# 05.net
KiCad netlist of a schematic drawn in Altium Designer
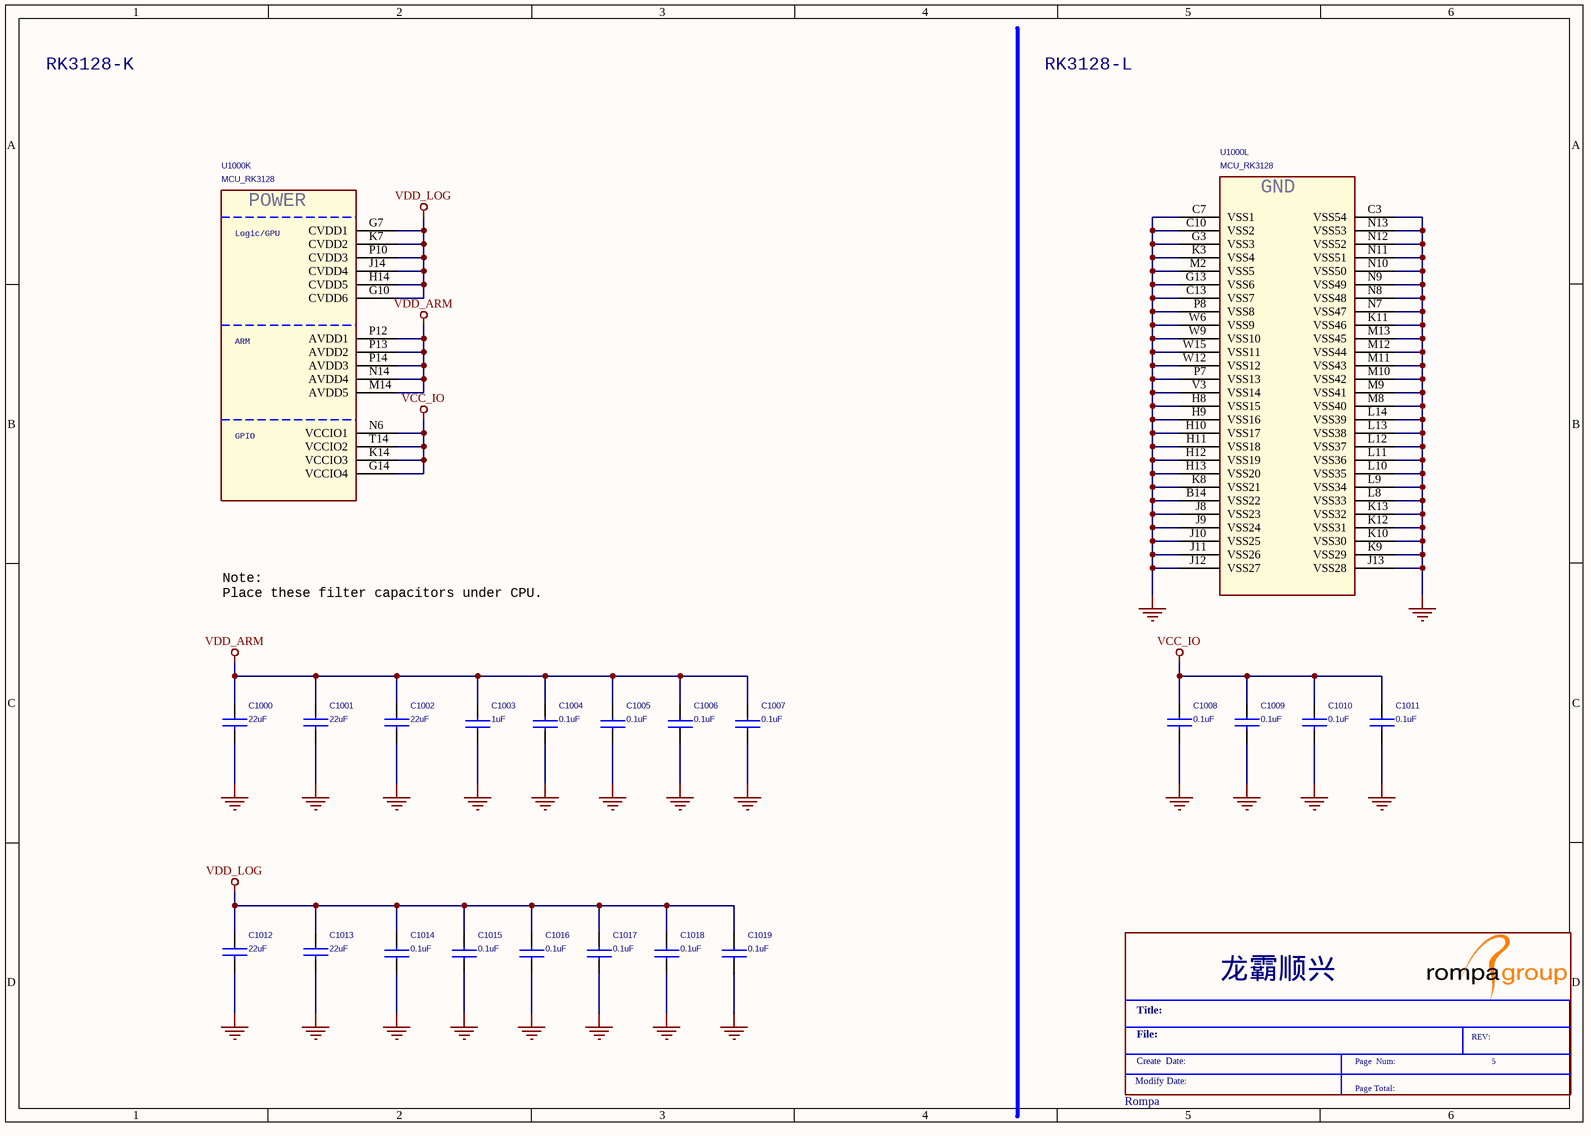
[diagram p0: 05.SchDoc]

(export (version "E")
  (design (tool "Eeschema 10.0.6"))
  (components
    (comp (ref "*")
      (value "Rompa")
      (fields (field (name "SCHEMATIC PAGE NUMBER") "5"))
      (libsource (lib "RK3128_BETA_V03_20151231_Library") (part "Rompa"))
    )
    (comp (ref "C1000")
      (value "22uF")
      (footprint "C0402")
      (description "RoHS CHIP CAP 22uF +10/-10% X5R")
      (libsource (lib "*") (part "CAP NP"))
    )
    (comp (ref "C1001")
      (value "22uF")
      (footprint "C0402")
      (description "RoHS CHIP CAP 22uF +10/-10% X5R")
      (libsource (lib "*") (part "CAP NP"))
    )
    (comp (ref "C1002")
      (value "22uF")
      (footprint "C0402")
      (description "RoHS CHIP CAP 22uF +10/-10% X5R")
      (libsource (lib "*") (part "CAP NP"))
    )
    (comp (ref "C1003")
      (value "1uF")
      (footprint "C0402")
      (description "RoHS CHIP CAP 1uF +10/-10% X5R")
      (libsource (lib "*") (part "CAP NP"))
    )
    (comp (ref "C1004")
      (value "0.1uF")
      (footprint "C0402")
      (description "RoHS CHIP CAP 0.1uF +10/-10% X7R")
      (libsource (lib "*") (part "CAP NP"))
    )
    (comp (ref "C1005")
      (value "0.1uF")
      (footprint "C0402")
      (description "RoHS CHIP CAP 0.1uF +10/-10% X7R")
      (libsource (lib "*") (part "CAP NP"))
    )
    (comp (ref "C1006")
      (value "0.1uF")
      (footprint "C0402")
      (description "RoHS CHIP CAP 0.1uF +10/-10% X7R")
      (libsource (lib "*") (part "CAP NP"))
    )
    (comp (ref "C1007")
      (value "0.1uF")
      (footprint "C0402")
      (description "RoHS CHIP CAP 0.1uF +10/-10% X7R")
      (libsource (lib "*") (part "CAP NP"))
    )
    (comp (ref "C1008")
      (value "0.1uF")
      (footprint "C0402")
      (description "RoHS CHIP CAP 0.1uF +10/-10% X7R")
      (libsource (lib "*") (part "CAP NP"))
    )
    (comp (ref "C1009")
      (value "0.1uF")
      (footprint "C0402")
      (description "RoHS CHIP CAP 0.1uF +10/-10% X7R")
      (libsource (lib "*") (part "CAP NP"))
    )
    (comp (ref "C1010")
      (value "0.1uF")
      (footprint "C0402")
      (description "RoHS CHIP CAP 0.1uF +10/-10% X7R")
      (libsource (lib "*") (part "CAP NP"))
    )
    (comp (ref "C1011")
      (value "0.1uF")
      (footprint "C0402")
      (description "RoHS CHIP CAP 0.1uF +10/-10% X7R")
      (libsource (lib "*") (part "CAP NP"))
    )
    (comp (ref "C1012")
      (value "22uF")
      (footprint "C0402")
      (description "RoHS CHIP CAP 22uF +10/-10% X5R")
      (libsource (lib "*") (part "CAP NP"))
    )
    (comp (ref "C1013")
      (value "22uF")
      (footprint "C0402")
      (description "RoHS CHIP CAP 22uF +10/-10% X5R")
      (libsource (lib "*") (part "CAP NP"))
    )
    (comp (ref "C1014")
      (value "0.1uF")
      (footprint "C0402")
      (description "RoHS CHIP CAP 0.1uF +10/-10% X7R")
      (libsource (lib "*") (part "CAP NP"))
    )
    (comp (ref "C1015")
      (value "0.1uF")
      (footprint "C0402")
      (description "RoHS CHIP CAP 0.1uF +10/-10% X7R")
      (libsource (lib "*") (part "CAP NP"))
    )
    (comp (ref "C1016")
      (value "0.1uF")
      (footprint "C0402")
      (description "RoHS CHIP CAP 0.1uF +10/-10% X7R")
      (libsource (lib "*") (part "CAP NP"))
    )
    (comp (ref "C1017")
      (value "0.1uF")
      (footprint "C0402")
      (description "RoHS CHIP CAP 0.1uF +10/-10% X7R")
      (libsource (lib "*") (part "CAP NP"))
    )
    (comp (ref "C1018")
      (value "0.1uF")
      (footprint "C0402")
      (description "RoHS CHIP CAP 0.1uF +10/-10% X7R")
      (libsource (lib "*") (part "CAP NP"))
    )
    (comp (ref "C1019")
      (value "0.1uF")
      (footprint "C0402")
      (description "RoHS CHIP CAP 0.1uF +10/-10% X7R")
      (libsource (lib "*") (part "CAP NP"))
    )
    (comp (ref "U1000")
      (value "MCU_RK3128")
      (footprint "BGA316-14X14-0.65")
      (libsource (lib "*") (part "MCU_RK3128"))
    )
  )
  (nets
    (net (code "1") (name "GND") (class "Default")
      (node (ref "C1000") (pin "2") (pinfunction "2_2") (pintype "passive"))
      (node (ref "C1001") (pin "2") (pinfunction "2_2") (pintype "passive"))
      (node (ref "C1002") (pin "2") (pinfunction "2_2") (pintype "passive"))
      (node (ref "C1003") (pin "1") (pinfunction "1_1") (pintype "passive"))
      (node (ref "C1004") (pin "1") (pinfunction "1_1") (pintype "passive"))
      (node (ref "C1005") (pin "1") (pinfunction "1_1") (pintype "passive"))
      (node (ref "C1006") (pin "1") (pinfunction "1_1") (pintype "passive"))
      (node (ref "C1007") (pin "1") (pinfunction "1_1") (pintype "passive"))
      (node (ref "C1008") (pin "2") (pinfunction "2_2") (pintype "passive"))
      (node (ref "C1009") (pin "2") (pinfunction "2_2") (pintype "passive"))
      (node (ref "C1010") (pin "2") (pinfunction "2_2") (pintype "passive"))
      (node (ref "C1011") (pin "2") (pinfunction "2_2") (pintype "passive"))
      (node (ref "C1012") (pin "2") (pinfunction "2_2") (pintype "passive"))
      (node (ref "C1013") (pin "2") (pinfunction "2_2") (pintype "passive"))
      (node (ref "C1014") (pin "1") (pinfunction "1_1") (pintype "passive"))
      (node (ref "C1015") (pin "1") (pinfunction "1_1") (pintype "passive"))
      (node (ref "C1016") (pin "1") (pinfunction "1_1") (pintype "passive"))
      (node (ref "C1017") (pin "1") (pinfunction "1_1") (pintype "passive"))
      (node (ref "C1018") (pin "1") (pinfunction "1_1") (pintype "passive"))
      (node (ref "C1019") (pin "1") (pinfunction "1_1") (pintype "passive"))
      (node (ref "U1000") (pin "B14") (pinfunction "VSS22_B14") (pintype "passive"))
      (node (ref "U1000") (pin "C10") (pinfunction "VSS2_C10") (pintype "passive"))
      (node (ref "U1000") (pin "C13") (pinfunction "VSS7_C13") (pintype "passive"))
      (node (ref "U1000") (pin "C3") (pinfunction "VSS54_C3") (pintype "passive"))
      (node (ref "U1000") (pin "C7") (pinfunction "VSS1_C7") (pintype "passive"))
      (node (ref "U1000") (pin "G13") (pinfunction "VSS6_G13") (pintype "passive"))
      (node (ref "U1000") (pin "G3") (pinfunction "VSS3_G3") (pintype "passive"))
      (node (ref "U1000") (pin "H10") (pinfunction "VSS17_H10") (pintype "passive"))
      (node (ref "U1000") (pin "H11") (pinfunction "VSS18_H11") (pintype "passive"))
      (node (ref "U1000") (pin "H12") (pinfunction "VSS19_H12") (pintype "passive"))
      (node (ref "U1000") (pin "H13") (pinfunction "VSS20_H13") (pintype "passive"))
      (node (ref "U1000") (pin "H8") (pinfunction "VSS15_H8") (pintype "passive"))
      (node (ref "U1000") (pin "H9") (pinfunction "VSS16_H9") (pintype "passive"))
      (node (ref "U1000") (pin "J10") (pinfunction "VSS25_J10") (pintype "passive"))
      (node (ref "U1000") (pin "J11") (pinfunction "VSS26_J11") (pintype "passive"))
      (node (ref "U1000") (pin "J12") (pinfunction "VSS27_J12") (pintype "passive"))
      (node (ref "U1000") (pin "J13") (pinfunction "VSS28_J13") (pintype "passive"))
      (node (ref "U1000") (pin "J8") (pinfunction "VSS23_J8") (pintype "passive"))
      (node (ref "U1000") (pin "J9") (pinfunction "VSS24_J9") (pintype "passive"))
      (node (ref "U1000") (pin "K10") (pinfunction "VSS30_K10") (pintype "passive"))
      (node (ref "U1000") (pin "K11") (pinfunction "VSS46_K11") (pintype "passive"))
      (node (ref "U1000") (pin "K12") (pinfunction "VSS31_K12") (pintype "passive"))
      (node (ref "U1000") (pin "K13") (pinfunction "VSS32_K13") (pintype "passive"))
      (node (ref "U1000") (pin "K3") (pinfunction "VSS4_K3") (pintype "passive"))
      (node (ref "U1000") (pin "K8") (pinfunction "VSS21_K8") (pintype "passive"))
      (node (ref "U1000") (pin "K9") (pinfunction "VSS29_K9") (pintype "passive"))
      (node (ref "U1000") (pin "L10") (pinfunction "VSS35_L10") (pintype "passive"))
      (node (ref "U1000") (pin "L11") (pinfunction "VSS36_L11") (pintype "passive"))
      (node (ref "U1000") (pin "L12") (pinfunction "VSS37_L12") (pintype "passive"))
      (node (ref "U1000") (pin "L13") (pinfunction "VSS38_L13") (pintype "passive"))
      (node (ref "U1000") (pin "L14") (pinfunction "VSS39_L14") (pintype "passive"))
      (node (ref "U1000") (pin "L8") (pinfunction "VSS33_L8") (pintype "passive"))
      (node (ref "U1000") (pin "L9") (pinfunction "VSS34_L9") (pintype "passive"))
      (node (ref "U1000") (pin "M10") (pinfunction "VSS42_M10") (pintype "passive"))
      (node (ref "U1000") (pin "M11") (pinfunction "VSS43_M11") (pintype "passive"))
      (node (ref "U1000") (pin "M12") (pinfunction "VSS44_M12") (pintype "passive"))
      (node (ref "U1000") (pin "M13") (pinfunction "VSS45_M13") (pintype "passive"))
      (node (ref "U1000") (pin "M2") (pinfunction "VSS5_M2") (pintype "passive"))
      (node (ref "U1000") (pin "M8") (pinfunction "VSS40_M8") (pintype "passive"))
      (node (ref "U1000") (pin "M9") (pinfunction "VSS41_M9") (pintype "passive"))
      (node (ref "U1000") (pin "N10") (pinfunction "VSS50_N10") (pintype "passive"))
      (node (ref "U1000") (pin "N11") (pinfunction "VSS51_N11") (pintype "passive"))
      (node (ref "U1000") (pin "N12") (pinfunction "VSS52_N12") (pintype "passive"))
      (node (ref "U1000") (pin "N13") (pinfunction "VSS53_N13") (pintype "passive"))
      (node (ref "U1000") (pin "N7") (pinfunction "VSS47_N7") (pintype "passive"))
      (node (ref "U1000") (pin "N8") (pinfunction "VSS48_N8") (pintype "passive"))
      (node (ref "U1000") (pin "N9") (pinfunction "VSS49_N9") (pintype "passive"))
      (node (ref "U1000") (pin "P7") (pinfunction "VSS13_P7") (pintype "passive"))
      (node (ref "U1000") (pin "P8") (pinfunction "VSS8_P8") (pintype "passive"))
      (node (ref "U1000") (pin "V3") (pinfunction "VSS14_V3") (pintype "passive"))
      (node (ref "U1000") (pin "W12") (pinfunction "VSS12_W12") (pintype "passive"))
      (node (ref "U1000") (pin "W15") (pinfunction "VSS11_W15") (pintype "passive"))
      (node (ref "U1000") (pin "W6") (pinfunction "VSS9_W6") (pintype "passive"))
      (node (ref "U1000") (pin "W9") (pinfunction "VSS10_W9") (pintype "passive"))
    )
    (net (code "2") (name "VCC_IO") (class "Default")
      (node (ref "C1008") (pin "1") (pinfunction "1_1") (pintype "passive"))
      (node (ref "C1009") (pin "1") (pinfunction "1_1") (pintype "passive"))
      (node (ref "C1010") (pin "1") (pinfunction "1_1") (pintype "passive"))
      (node (ref "C1011") (pin "1") (pinfunction "1_1") (pintype "passive"))
      (node (ref "U1000") (pin "G14") (pinfunction "VCCIO4_G14") (pintype "passive"))
      (node (ref "U1000") (pin "K14") (pinfunction "VCCIO3_K14") (pintype "passive"))
      (node (ref "U1000") (pin "N6") (pinfunction "VCCIO1_N6") (pintype "passive"))
      (node (ref "U1000") (pin "T14") (pinfunction "VCCIO2_T14") (pintype "passive"))
    )
    (net (code "3") (name "VDD_ARM") (class "Default")
      (node (ref "C1000") (pin "1") (pinfunction "1_1") (pintype "passive"))
      (node (ref "C1001") (pin "1") (pinfunction "1_1") (pintype "passive"))
      (node (ref "C1002") (pin "1") (pinfunction "1_1") (pintype "passive"))
      (node (ref "C1003") (pin "2") (pinfunction "2_2") (pintype "passive"))
      (node (ref "C1004") (pin "2") (pinfunction "2_2") (pintype "passive"))
      (node (ref "C1005") (pin "2") (pinfunction "2_2") (pintype "passive"))
      (node (ref "C1006") (pin "2") (pinfunction "2_2") (pintype "passive"))
      (node (ref "C1007") (pin "2") (pinfunction "2_2") (pintype "passive"))
      (node (ref "U1000") (pin "M14") (pinfunction "AVDD5_M14") (pintype "passive"))
      (node (ref "U1000") (pin "N14") (pinfunction "AVDD4_N14") (pintype "passive"))
      (node (ref "U1000") (pin "P12") (pinfunction "AVDD1_P12") (pintype "passive"))
      (node (ref "U1000") (pin "P13") (pinfunction "AVDD2_P13") (pintype "passive"))
      (node (ref "U1000") (pin "P14") (pinfunction "AVDD3_P14") (pintype "passive"))
    )
    (net (code "4") (name "VDD_LOG") (class "Default")
      (node (ref "C1012") (pin "1") (pinfunction "1_1") (pintype "passive"))
      (node (ref "C1013") (pin "1") (pinfunction "1_1") (pintype "passive"))
      (node (ref "C1014") (pin "2") (pinfunction "2_2") (pintype "passive"))
      (node (ref "C1015") (pin "2") (pinfunction "2_2") (pintype "passive"))
      (node (ref "C1016") (pin "2") (pinfunction "2_2") (pintype "passive"))
      (node (ref "C1017") (pin "2") (pinfunction "2_2") (pintype "passive"))
      (node (ref "C1018") (pin "2") (pinfunction "2_2") (pintype "passive"))
      (node (ref "C1019") (pin "2") (pinfunction "2_2") (pintype "passive"))
      (node (ref "U1000") (pin "G10") (pinfunction "CVDD6_G10") (pintype "passive"))
      (node (ref "U1000") (pin "G7") (pinfunction "CVDD1_G7") (pintype "passive"))
      (node (ref "U1000") (pin "H14") (pinfunction "CVDD5_H14") (pintype "passive"))
      (node (ref "U1000") (pin "J14") (pinfunction "CVDD4_J14") (pintype "passive"))
      (node (ref "U1000") (pin "K7") (pinfunction "CVDD2_K7") (pintype "passive"))
      (node (ref "U1000") (pin "P10") (pinfunction "CVDD3_P10") (pintype "passive"))
    )
  )
)
